# schematic.net
KiCad netlist of a schematic drawn in Altium Designer
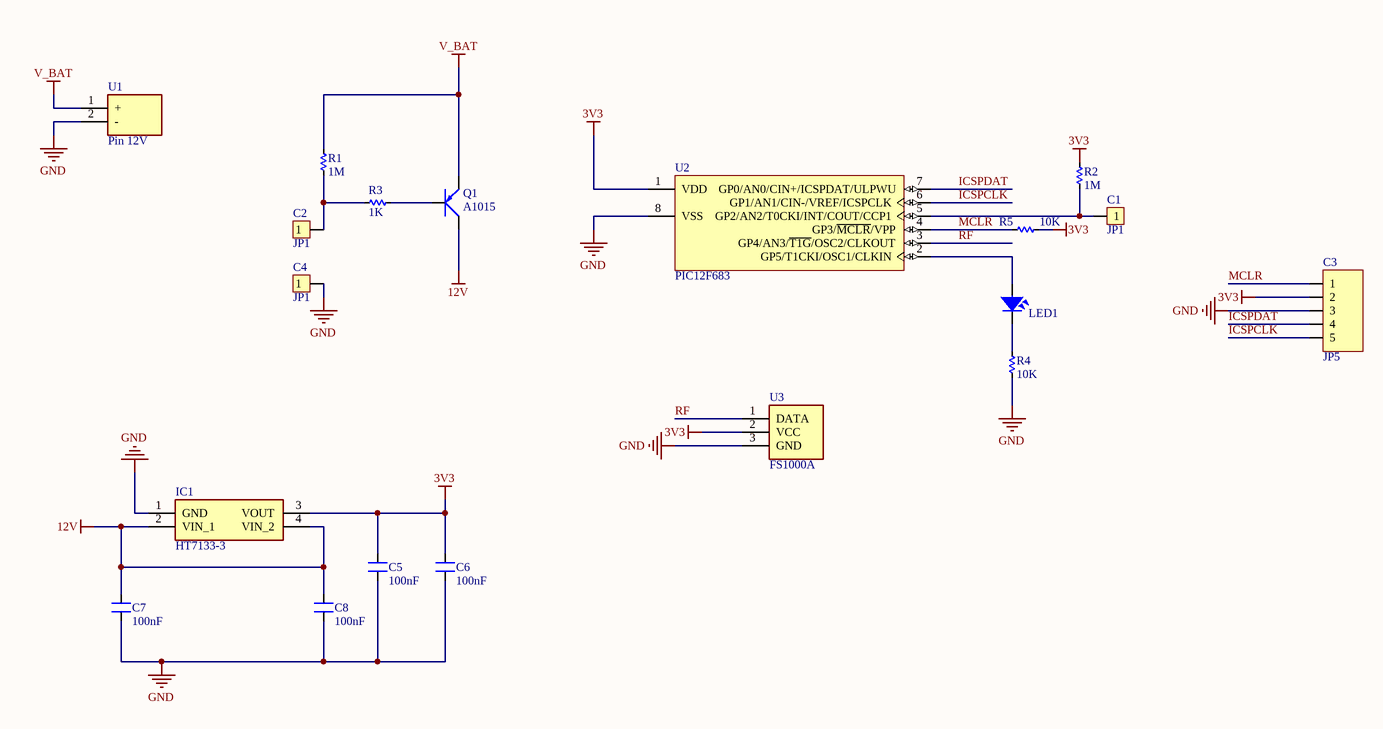
[diagram p0: schematic.SchDoc]

(export (version "E")
  (design (tool "Eeschema 10.0.6"))
  (components
    (comp (ref "C1")
      (value "JP1")
      (footprint "JP1-D1T")
      (description "WR-PHD 2.54 mm Angled Socket Header")
      (fields
        (field (name "MANUFACTURER") "Würth Elektronik eiSos GmbH")
        (field (name "PARTNO") "613002143121")
        (field (name "CREATED BY") "Karrer Zheng")
      )
      (libsource (lib "LIBRARY") (part "JP1"))
    )
    (comp (ref "C2")
      (value "JP1")
      (footprint "JP1-D1T")
      (description "WR-PHD 2.54 mm Angled Socket Header")
      (fields
        (field (name "MANUFACTURER") "Würth Elektronik eiSos GmbH")
        (field (name "PARTNO") "613002143121")
        (field (name "CREATED BY") "Karrer Zheng")
      )
      (libsource (lib "") (part "JP1_1"))
    )
    (comp (ref "C3")
      (value "JP5")
      (footprint "JP5-D1T")
      (description "WR-PHD 2.54 mm Angled Socket Header")
      (fields
        (field (name "MANUFACTURER") "Würth Elektronik eiSos GmbH")
        (field (name "PARTNO") "613005143121")
        (field (name "CREATED BY") "Karrer Zheng")
      )
      (libsource (lib "LIBRARY") (part "JP5"))
    )
    (comp (ref "C4")
      (value "JP1")
      (footprint "JP1-D1T")
      (description "WR-PHD 2.54 mm Angled Socket Header")
      (fields
        (field (name "MANUFACTURER") "Würth Elektronik eiSos GmbH")
        (field (name "PARTNO") "613002143121")
        (field (name "CREATED BY") "Karrer Zheng")
      )
      (libsource (lib "") (part "JP1_1"))
    )
    (comp (ref "C5") (value "100nF") (footprint "CN-SMD-0603") (libsource (lib "LIBRARY") (part "CN")))
    (comp (ref "C6") (value "100nF") (footprint "CN-SMD-0603") (libsource (lib "LIBRARY") (part "CN")))
    (comp (ref "C7") (value "100nF") (footprint "CN-SMD-0603") (libsource (lib "LIBRARY") (part "CN")))
    (comp (ref "C8") (value "100nF") (footprint "CN-SMD-0603") (libsource (lib "LIBRARY") (part "CN")))
    (comp (ref "IC1")
      (value "HT7133-3")
      (footprint "SamacSys:AZ1117CR33TRG1")
      (description "Integrated Circuit")
      (fields
        (field (name "MANUFACTURER_PART_NUMBER") "AP2204RA-5.0TRG1")
        (field (name "MOUSER PART NUMBER") "621-AP2204RA-5.0TRG1")
      )
      (libsource (lib "*") (part "AP2204RA-5.0TRG1"))
    )
    (comp (ref "LED1")
      (value "LED")
      (footprint "LED-3MM-GREEN")
      (description "LED Single colour Green and Red")
      (libsource (lib "LIBRARY") (part "LED"))
    )
    (comp (ref "Q1")
      (value "A1015")
      (footprint "SOT23B")
      (description "PNP 600mW, ECB")
      (libsource (lib "electronicvn-library1") (part "A1015"))
    )
    (comp (ref "R1")
      (value "1M")
      (footprint "RES-SMD-0603")
      (description "Resistor")
      (fields
        (field (name "MANUFACTURER") "Generic Components")
        (field (name "PUBLISHER") "Altium Hobart Technology Centre")
      )
      (libsource (lib "LIBRARY") (part "Res-SMD"))
    )
    (comp (ref "R2")
      (value "1M")
      (footprint "RES-SMD-0603")
      (description "Resistor")
      (fields
        (field (name "MANUFACTURER") "Generic Components")
        (field (name "PUBLISHER") "Altium Hobart Technology Centre")
      )
      (libsource (lib "LIBRARY") (part "Res-SMD"))
    )
    (comp (ref "R3")
      (value "1K")
      (footprint "RES-SMD-0603")
      (description "Resistor")
      (fields
        (field (name "MANUFACTURER") "Generic Components")
        (field (name "PUBLISHER") "Altium Hobart Technology Centre")
      )
      (libsource (lib "LIBRARY") (part "Res-SMD"))
    )
    (comp (ref "R4")
      (value "10K")
      (footprint "RES-SMD-0603")
      (description "Resistor")
      (fields
        (field (name "MANUFACTURER") "Generic Components")
        (field (name "PUBLISHER") "Altium Hobart Technology Centre")
      )
      (libsource (lib "LIBRARY") (part "Res-SMD"))
    )
    (comp (ref "R5")
      (value "10K")
      (footprint "RES-SMD-0603")
      (description "Resistor")
      (fields
        (field (name "MANUFACTURER") "Generic Components")
        (field (name "PUBLISHER") "Altium Hobart Technology Centre")
      )
      (libsource (lib "LIBRARY") (part "Res-SMD"))
    )
    (comp (ref "U1")
      (value "Pin 12V")
      (footprint "pin_alkaline")
      (libsource (lib "Schlib1") (part "Pin Alkaline 12V"))
    )
    (comp (ref "U2") (value "PIC12F683") (footprint "SO8") (libsource (lib "LIBRARY") (part "PIC12F683")))
    (comp (ref "U3") (value "FS1000A") (footprint "fs1000a") (libsource (lib "Schlib1") (part "FS1000A")))
  )
  (nets
    (net (code "1") (name "/ICSPCLK") (class "Default")
      (node (ref "C3") (pin "5") (pinfunction "5_5") (pintype "passive"))
      (node (ref "U2") (pin "6") (pinfunction "GP1/AN1/CIN-/VREF/ICSPCLK_6") (pintype "bidirectional"))
    )
    (net (code "2") (name "/ICSPDAT") (class "Default")
      (node (ref "C3") (pin "4") (pinfunction "4_4") (pintype "passive"))
      (node (ref "U2") (pin "7") (pinfunction "GP0/AN0/CIN+/ICSPDAT/ULPWU_7") (pintype "bidirectional"))
    )
    (net (code "3") (name "/MCLR") (class "Default")
      (node (ref "C3") (pin "1") (pinfunction "1_1") (pintype "passive"))
      (node (ref "R5") (pin "2") (pinfunction "2_2") (pintype "passive"))
      (node (ref "U2") (pin "4") (pinfunction "GP3/~{MCLR}/VPP_4") (pintype "bidirectional"))
    )
    (net (code "4") (name "/RF") (class "Default")
      (node (ref "U2") (pin "3") (pinfunction "GP4/AN3/~{T1G}/OSC2/CLKOUT_3") (pintype "bidirectional"))
      (node (ref "U3") (pin "1") (pinfunction "DATA_1") (pintype "passive"))
    )
    (net (code "5") (name "3V3") (class "Default")
      (node (ref "C3") (pin "2") (pinfunction "2_2") (pintype "passive"))
      (node (ref "C5") (pin "2") (pinfunction "2_2") (pintype "passive"))
      (node (ref "C6") (pin "2") (pinfunction "2_2") (pintype "passive"))
      (node (ref "IC1") (pin "3") (pinfunction "VOUT_3") (pintype "passive"))
      (node (ref "R2") (pin "1") (pinfunction "1_1") (pintype "passive"))
      (node (ref "R5") (pin "1") (pinfunction "1_1") (pintype "passive"))
      (node (ref "U2") (pin "1") (pinfunction "VDD_1") (pintype "power_in"))
      (node (ref "U3") (pin "2") (pinfunction "VCC_2") (pintype "passive"))
    )
    (net (code "6") (name "12V") (class "Default")
      (node (ref "C7") (pin "2") (pinfunction "2_2") (pintype "passive"))
      (node (ref "C8") (pin "2") (pinfunction "2_2") (pintype "passive"))
      (node (ref "IC1") (pin "2") (pinfunction "VIN_1_2") (pintype "passive"))
      (node (ref "IC1") (pin "4") (pinfunction "VIN_2_4") (pintype "passive"))
      (node (ref "Q1") (pin "2") (pinfunction "C_2") (pintype "passive"))
    )
    (net (code "7") (name "GND") (class "Default")
      (node (ref "C3") (pin "3") (pinfunction "3_3") (pintype "passive"))
      (node (ref "C4") (pin "1") (pinfunction "1_1") (pintype "passive"))
      (node (ref "C5") (pin "1") (pinfunction "1_1") (pintype "passive"))
      (node (ref "C6") (pin "1") (pinfunction "1_1") (pintype "passive"))
      (node (ref "C7") (pin "1") (pinfunction "1_1") (pintype "passive"))
      (node (ref "C8") (pin "1") (pinfunction "1_1") (pintype "passive"))
      (node (ref "IC1") (pin "1") (pinfunction "GND_1") (pintype "passive"))
      (node (ref "R4") (pin "2") (pinfunction "2_2") (pintype "passive"))
      (node (ref "U1") (pin "2") (pinfunction "-_2") (pintype "passive"))
      (node (ref "U2") (pin "8") (pinfunction "VSS_8") (pintype "power_in"))
      (node (ref "U3") (pin "3") (pinfunction "GND_3") (pintype "passive"))
    )
    (net (code "8") (name "Net-(C2-Pad1)") (class "Default")
      (node (ref "C2") (pin "1") (pinfunction "1_1") (pintype "passive"))
      (node (ref "R1") (pin "2") (pinfunction "2_2") (pintype "passive"))
      (node (ref "R3") (pin "1") (pinfunction "1_1") (pintype "passive"))
    )
    (net (code "9") (name "Net-(LED1-Pad2)") (class "Default")
      (node (ref "LED1") (pin "2") (pinfunction "2_2") (pintype "passive"))
      (node (ref "R4") (pin "1") (pinfunction "1_1") (pintype "passive"))
    )
    (net (code "10") (name "Net-(Q1-B)") (class "Default")
      (node (ref "Q1") (pin "3") (pinfunction "B_3") (pintype "passive"))
      (node (ref "R3") (pin "2") (pinfunction "2_2") (pintype "passive"))
    )
    (net (code "11") (name "Net-(U2-GP2{slash}AN2{slash}T0CKI{slash}INT{slash}COUT{slash}CCP1)") (class "Default")
      (node (ref "C1") (pin "1") (pinfunction "1_1") (pintype "passive"))
      (node (ref "R2") (pin "2") (pinfunction "2_2") (pintype "passive"))
      (node (ref "U2") (pin "5") (pinfunction "GP2/AN2/T0CKI/INT/COUT/CCP1_5") (pintype "bidirectional"))
    )
    (net (code "12") (name "Net-(U2-GP5{slash}T1CKI{slash}OSC1{slash}CLKIN)") (class "Default")
      (node (ref "LED1") (pin "1") (pinfunction "1_1") (pintype "passive"))
      (node (ref "U2") (pin "2") (pinfunction "GP5/T1CKI/OSC1/CLKIN_2") (pintype "bidirectional"))
    )
    (net (code "13") (name "V_BAT") (class "Default")
      (node (ref "Q1") (pin "1") (pinfunction "E_1") (pintype "passive"))
      (node (ref "R1") (pin "1") (pinfunction "1_1") (pintype "passive"))
      (node (ref "U1") (pin "1") (pinfunction "+_1") (pintype "passive"))
    )
  )
)
